# 780-00019_Rev3_Pg1.net
KiCad netlist of a schematic drawn in Altium Designer
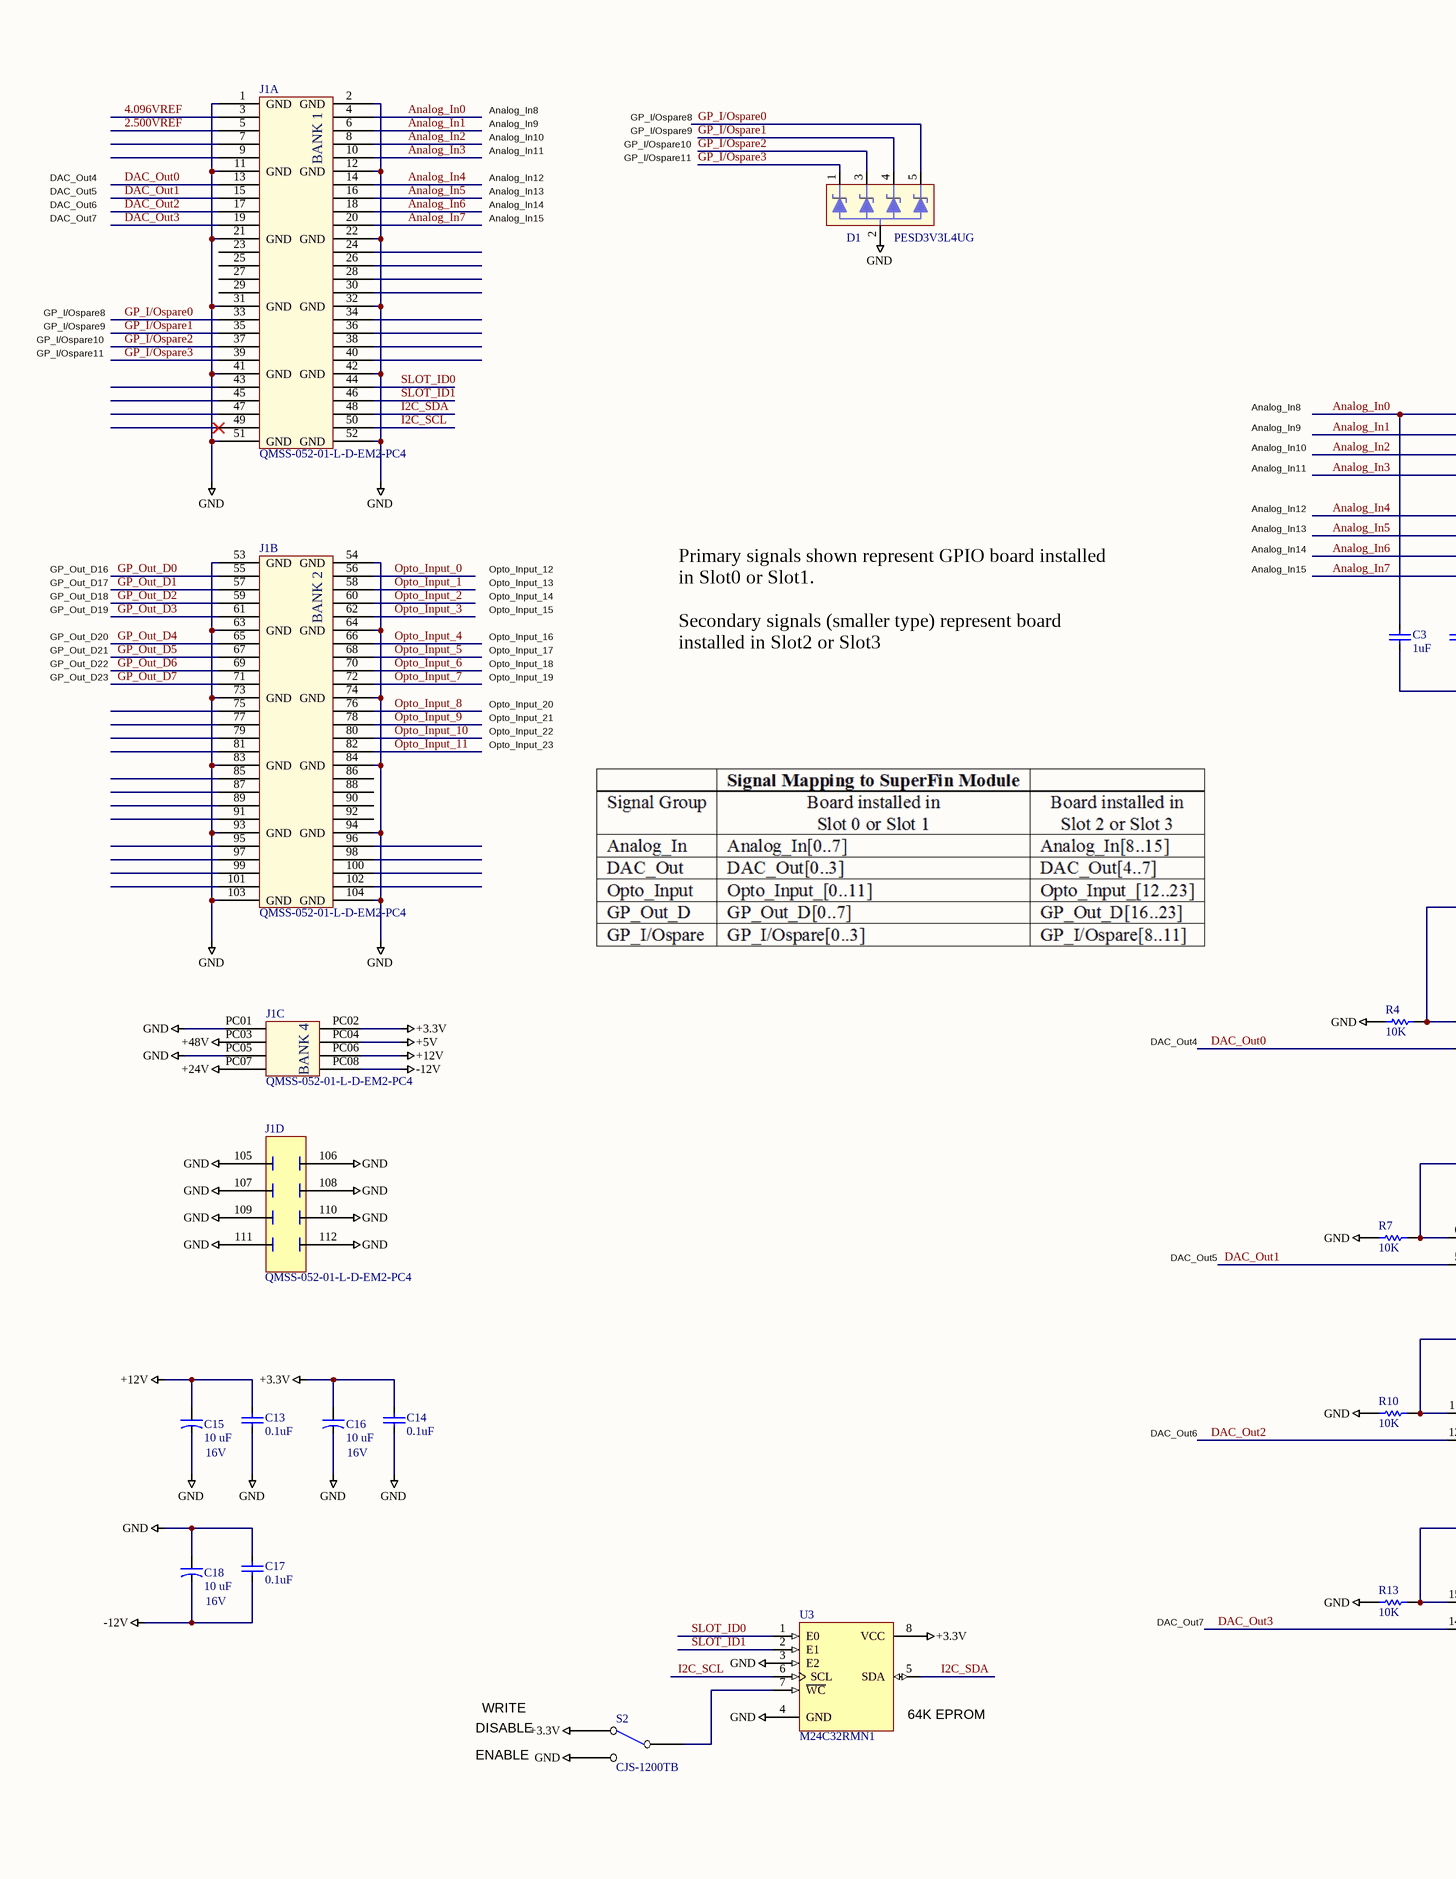
[diagram p0: 780-00019 Rev3 Pg1.SchDoc, left]
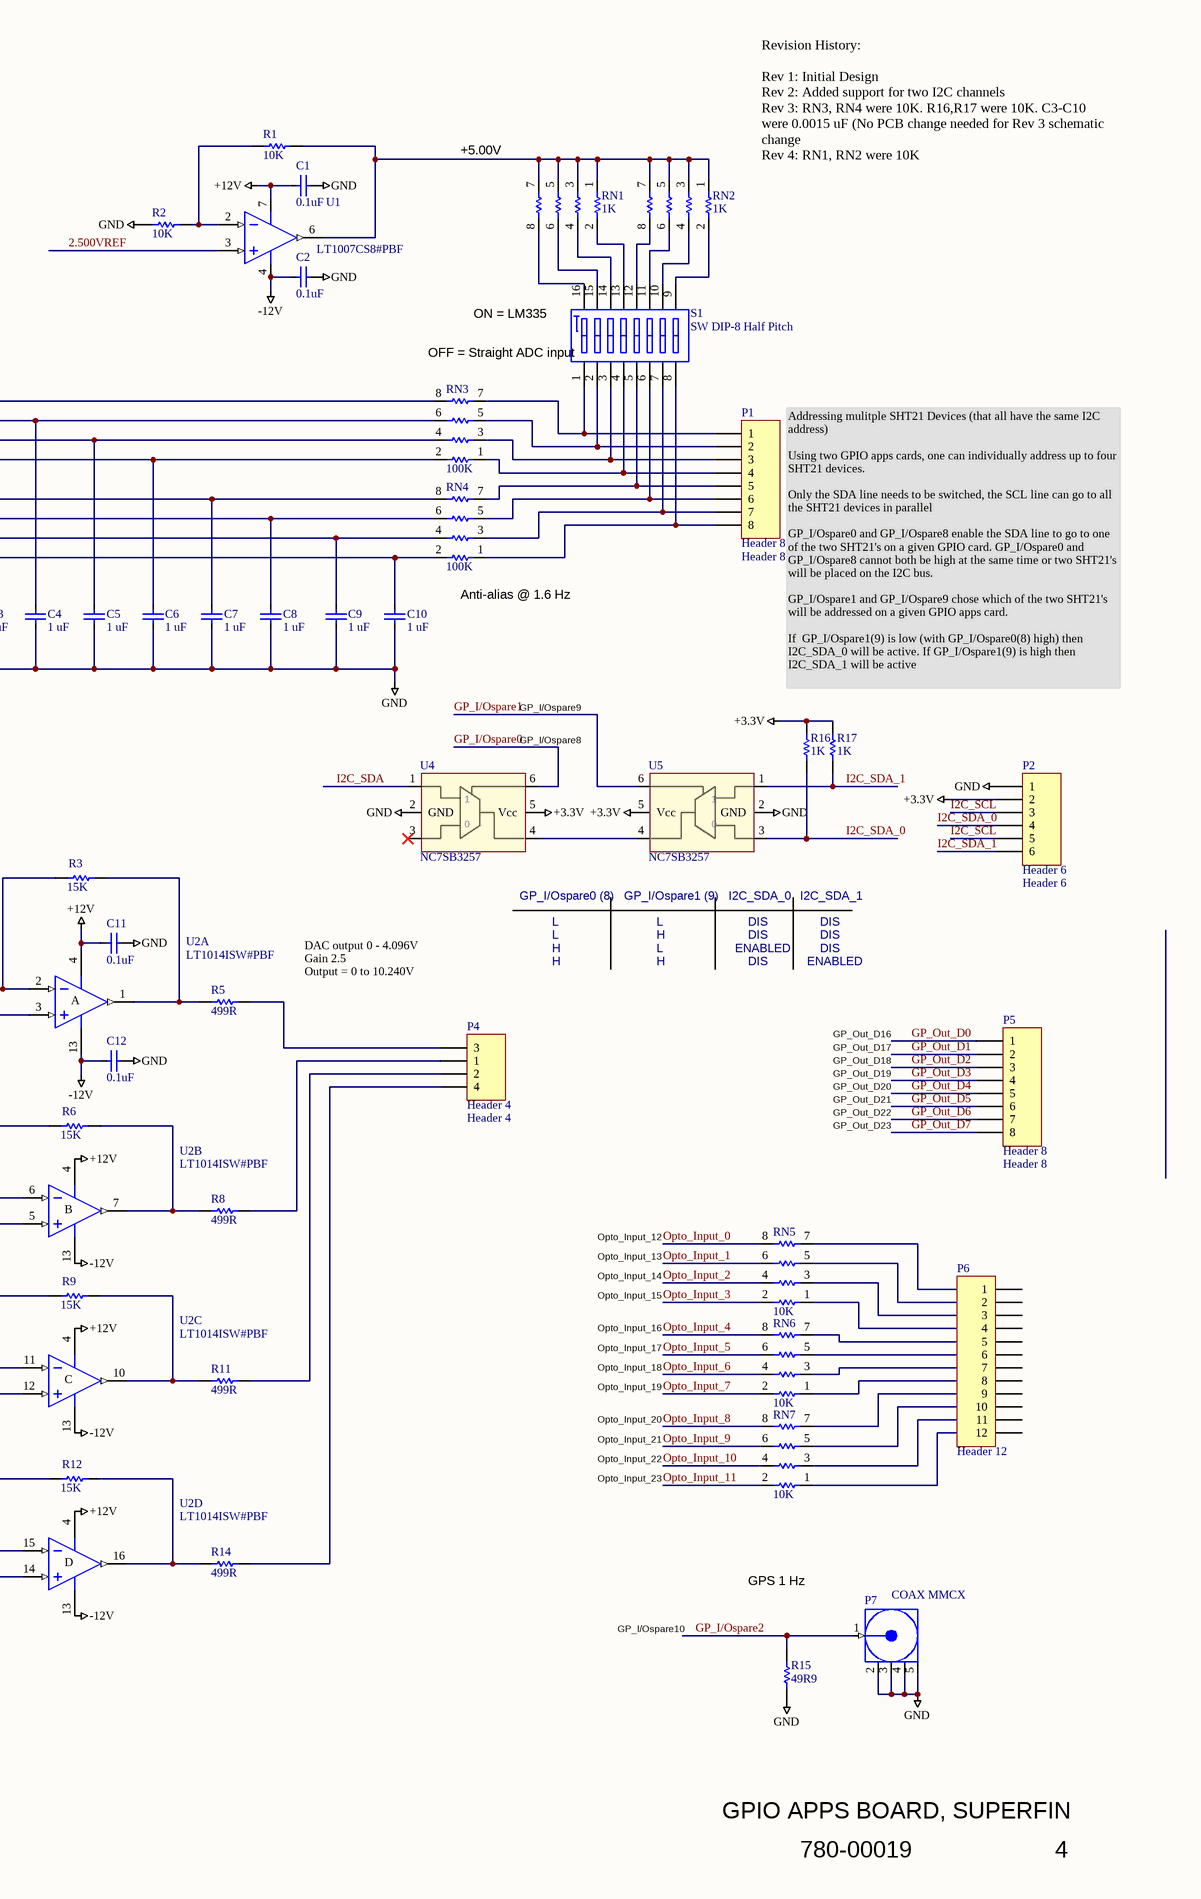
[diagram p1: 780-00019 Rev3 Pg1.SchDoc, right]

(export (version "E")
  (design (tool "Eeschema 10.0.6"))
  (components
    (comp (ref "C1")
      (value "0.1uF")
      (footprint "SMD_0805")
      (description "Capacitor")
      (fields (field (name "Comment") "Cap SMD"))
      (libsource (lib "Richs Schematic Components") (part "Cap SMD"))
    )
    (comp (ref "C2")
      (value "0.1uF")
      (footprint "SMD_0805")
      (description "Capacitor")
      (fields (field (name "Comment") "Cap SMD"))
      (libsource (lib "Richs Schematic Components") (part "Cap SMD"))
    )
    (comp (ref "C3")
      (value "1uF")
      (footprint "SMD_0805")
      (description "Capacitor NP0")
      (fields (field (name "MANUFACTURER") "Murata") (field (name "Comment") "Cap SMD"))
      (libsource (lib "Richs Schematic Components") (part "Cap SMD"))
    )
    (comp (ref "C4")
      (value "1 uF")
      (footprint "SMD_0805")
      (description "Capacitor NP0")
      (fields (field (name "MANUFACTURER") "Murata") (field (name "Comment") "Cap SMD"))
      (libsource (lib "Richs Schematic Components") (part "Cap SMD"))
    )
    (comp (ref "C5")
      (value "1 uF")
      (footprint "SMD_0805")
      (description "Capacitor NP0")
      (fields (field (name "MANUFACTURER") "Murata") (field (name "Comment") "Cap SMD"))
      (libsource (lib "Richs Schematic Components") (part "Cap SMD"))
    )
    (comp (ref "C6")
      (value "1 uF")
      (footprint "SMD_0805")
      (description "Capacitor NP0")
      (fields (field (name "MANUFACTURER") "Murata") (field (name "Comment") "Cap SMD"))
      (libsource (lib "Richs Schematic Components") (part "Cap SMD"))
    )
    (comp (ref "C7")
      (value "1 uF")
      (footprint "SMD_0805")
      (description "Capacitor NP0")
      (fields (field (name "MANUFACTURER") "Murata") (field (name "Comment") "Cap SMD"))
      (libsource (lib "Richs Schematic Components") (part "Cap SMD"))
    )
    (comp (ref "C8")
      (value "1 uF")
      (footprint "SMD_0805")
      (description "Capacitor NP0")
      (fields (field (name "MANUFACTURER") "Murata") (field (name "Comment") "Cap SMD"))
      (libsource (lib "Richs Schematic Components") (part "Cap SMD"))
    )
    (comp (ref "C9")
      (value "1 uF")
      (footprint "SMD_0805")
      (description "Capacitor NP0")
      (fields (field (name "MANUFACTURER") "Murata") (field (name "Comment") "Cap SMD"))
      (libsource (lib "Richs Schematic Components") (part "Cap SMD"))
    )
    (comp (ref "C10")
      (value "1 uF")
      (footprint "SMD_0805")
      (description "Capacitor NP0")
      (fields (field (name "MANUFACTURER") "Murata") (field (name "Comment") "Cap SMD"))
      (libsource (lib "Richs Schematic Components") (part "Cap SMD"))
    )
    (comp (ref "C11")
      (value "0.1uF")
      (footprint "SMD_0805")
      (description "Capacitor")
      (fields (field (name "Comment") "Cap SMD"))
      (libsource (lib "Richs Schematic Components") (part "Cap SMD"))
    )
    (comp (ref "C12")
      (value "0.1uF")
      (footprint "SMD_0805")
      (description "Capacitor")
      (fields (field (name "Comment") "Cap SMD"))
      (libsource (lib "Richs Schematic Components") (part "Cap SMD"))
    )
    (comp (ref "C13")
      (value "0.1uF")
      (footprint "SMD_0805")
      (description "Capacitor")
      (fields (field (name "Comment") "Cap SMD"))
      (libsource (lib "Richs Schematic Components") (part "Cap SMD"))
    )
    (comp (ref "C14")
      (value "0.1uF")
      (footprint "SMD_0805")
      (description "Capacitor")
      (fields (field (name "Comment") "Cap SMD"))
      (libsource (lib "Richs Schematic Components") (part "Cap SMD"))
    )
    (comp (ref "C15")
      (value "16V")
      (footprint "SMD_CAP_3216")
      (description "outline 3.2mm x 1.6mm")
      (fields (field (name "MANUFACTURER") "KEMET") (field (name "ALTIUM_VALUE") "10 uF"))
      (libsource (lib "Richs Schematic Components") (part "Cap Tant 16V"))
    )
    (comp (ref "C16")
      (value "16V")
      (footprint "SMD_CAP_3216")
      (description "outline 3.2mm x 1.6mm")
      (fields (field (name "MANUFACTURER") "KEMET") (field (name "ALTIUM_VALUE") "10 uF"))
      (libsource (lib "Richs Schematic Components") (part "Cap Tant 16V"))
    )
    (comp (ref "C17")
      (value "0.1uF")
      (footprint "SMD_0805")
      (description "Capacitor")
      (fields (field (name "Comment") "Cap SMD"))
      (libsource (lib "Richs Schematic Components") (part "Cap SMD"))
    )
    (comp (ref "C18")
      (value "16V")
      (footprint "SMD_CAP_3216")
      (description "outline 3.2mm x 1.6mm")
      (fields (field (name "MANUFACTURER") "KEMET") (field (name "ALTIUM_VALUE") "10 uF"))
      (libsource (lib "Richs Schematic Components") (part "Cap Tant 16V"))
    )
    (comp (ref "D1")
      (value "PESD3V3L4UG")
      (footprint "SOT-353")
      (description "Quad ESD Diode 3.3V")
      (fields (field (name "MANUFACTURER") "NXP"))
      (libsource (lib "Richs Schematic Components") (part "ESD Diode 3.3V Quad"))
    )
    (comp (ref "J1")
      (value "QMSS-052-01-L-D-EM2-PC4")
      (footprint "QMS EDGE PWR PINS - 104 pin")
      (description "SAMTEC QMSS EDGE W/PWR PINS")
      (fields (field (name "MANUFACTURER") "SAMTEC") (field (name "Comment") "QMSS-EM-PC4-104pin"))
      (libsource (lib "Richs Schematic Components") (part "QMSS-EM-PC4-104pin"))
    )
    (comp (ref "P1")
      (value "Header 8")
      (footprint "HDR1X8 for IDC")
      (description "Header, 8-Pin")
      (fields (field (name "MANUFACTURER") "tyco") (field (name "ALTIUM_VALUE") "Header 8"))
      (libsource (lib "Richs Schematic Components") (part "Header 8"))
    )
    (comp (ref "P2")
      (value "Header 6")
      (footprint "HDR1X6 for IDC")
      (description "Header, 6-Pin")
      (fields (field (name "ALTIUM_VALUE") "Header 6"))
      (libsource (lib "Richs Schematic Components") (part "Header 6"))
    )
    (comp (ref "P4")
      (value "Header 4")
      (footprint "HDR1X4 for IDC")
      (description "Header, 4-Pin")
      (fields (field (name "ALTIUM_VALUE") "Header 4"))
      (libsource (lib "Richs Schematic Components") (part "Header 4"))
    )
    (comp (ref "P5")
      (value "Header 8")
      (footprint "HDR1X8 for IDC")
      (description "Header, 8-Pin")
      (fields (field (name "MANUFACTURER") "tyco") (field (name "ALTIUM_VALUE") "Header 8"))
      (libsource (lib "Richs Schematic Components") (part "Header 8"))
    )
    (comp (ref "P6")
      (value "Header 12")
      (footprint "HDR1X12 for IDC")
      (description "Header, 12-Pin")
      (fields (field (name "MANUFACTURER") "Tyco"))
      (libsource (lib "Richs Schematic Components") (part "Header 12"))
    )
    (comp (ref "P7")
      (value "COAX MMCX")
      (footprint "Miscellaneous Connectors:MMCX2.54-V5")
      (description "RF Coaxial PCB Connector, MMCX; Thru-Hole, Vertical Mount Plug,  50 Ohm Impedance")
      (fields (field (name "MANUFACTURER") "Emerson"))
      (libsource (lib "Richs Schematic Components") (part "COAX-M"))
    )
    (comp (ref "R1")
      (value "10K")
      (footprint "SMD_0805")
      (description "Resistor 0805")
      (fields (field (name "MANUFACTURER") "Vishay/Dale") (field (name "Comment") "Res 0805"))
      (libsource (lib "Richs Schematic Components") (part "Res SMD"))
    )
    (comp (ref "R2")
      (value "10K")
      (footprint "SMD_0805")
      (description "Resistor 0805")
      (fields (field (name "MANUFACTURER") "Vishay/Dale") (field (name "Comment") "Res 0805"))
      (libsource (lib "Richs Schematic Components") (part "Res SMD"))
    )
    (comp (ref "R3")
      (value "15K")
      (footprint "SMD_0805")
      (description "Resistor 0805")
      (fields (field (name "MANUFACTURER") "Vishay/Dale") (field (name "Comment") "Res 0805"))
      (libsource (lib "Richs Schematic Components") (part "Res SMD"))
    )
    (comp (ref "R4")
      (value "10K")
      (footprint "SMD_0805")
      (description "Resistor 0805")
      (fields (field (name "MANUFACTURER") "Vishay/Dale") (field (name "Comment") "Res 0805"))
      (libsource (lib "Richs Schematic Components") (part "Res SMD"))
    )
    (comp (ref "R5")
      (value "499R")
      (footprint "SMD_0805")
      (description "Resistor 0805")
      (fields (field (name "MANUFACTURER") "Vishay/Dale") (field (name "Comment") "Res 0805"))
      (libsource (lib "Richs Schematic Components") (part "Res SMD"))
    )
    (comp (ref "R6")
      (value "15K")
      (footprint "SMD_0805")
      (description "Resistor 0805")
      (fields (field (name "MANUFACTURER") "Vishay/Dale") (field (name "Comment") "Res 0805"))
      (libsource (lib "Richs Schematic Components") (part "Res SMD"))
    )
    (comp (ref "R7")
      (value "10K")
      (footprint "SMD_0805")
      (description "Resistor 0805")
      (fields (field (name "MANUFACTURER") "Vishay/Dale") (field (name "Comment") "Res 0805"))
      (libsource (lib "Richs Schematic Components") (part "Res SMD"))
    )
    (comp (ref "R8")
      (value "499R")
      (footprint "SMD_0805")
      (description "Resistor 0805")
      (fields (field (name "MANUFACTURER") "Vishay/Dale") (field (name "Comment") "Res 0805"))
      (libsource (lib "Richs Schematic Components") (part "Res SMD"))
    )
    (comp (ref "R9")
      (value "15K")
      (footprint "SMD_0805")
      (description "Resistor 0805")
      (fields (field (name "MANUFACTURER") "Vishay/Dale") (field (name "Comment") "Res 0805"))
      (libsource (lib "Richs Schematic Components") (part "Res SMD"))
    )
    (comp (ref "R10")
      (value "10K")
      (footprint "SMD_0805")
      (description "Resistor 0805")
      (fields (field (name "MANUFACTURER") "Vishay/Dale") (field (name "Comment") "Res 0805"))
      (libsource (lib "Richs Schematic Components") (part "Res SMD"))
    )
    (comp (ref "R11")
      (value "499R")
      (footprint "SMD_0805")
      (description "Resistor 0805")
      (fields (field (name "MANUFACTURER") "Vishay/Dale") (field (name "Comment") "Res 0805"))
      (libsource (lib "Richs Schematic Components") (part "Res SMD"))
    )
    (comp (ref "R12")
      (value "15K")
      (footprint "SMD_0805")
      (description "Resistor 0805")
      (fields (field (name "MANUFACTURER") "Vishay/Dale") (field (name "Comment") "Res 0805"))
      (libsource (lib "Richs Schematic Components") (part "Res SMD"))
    )
    (comp (ref "R13")
      (value "10K")
      (footprint "SMD_0805")
      (description "Resistor 0805")
      (fields (field (name "MANUFACTURER") "Vishay/Dale") (field (name "Comment") "Res 0805"))
      (libsource (lib "Richs Schematic Components") (part "Res SMD"))
    )
    (comp (ref "R14")
      (value "499R")
      (footprint "SMD_0805")
      (description "Resistor 0805")
      (fields (field (name "MANUFACTURER") "Vishay/Dale") (field (name "Comment") "Res 0805"))
      (libsource (lib "Richs Schematic Components") (part "Res SMD"))
    )
    (comp (ref "R15")
      (value "49R9")
      (footprint "SMD_0805")
      (description "Resistor 0805")
      (fields (field (name "MANUFACTURER") "Vishay/Dale") (field (name "Comment") "Res 0805"))
      (libsource (lib "Richs Schematic Components") (part "Res SMD"))
    )
    (comp (ref "R16")
      (value "1K")
      (footprint "SMD_0805")
      (description "Resistor 0805")
      (fields (field (name "MANUFACTURER") "Vishay/Dale") (field (name "Comment") "Res 0805"))
      (libsource (lib "Richs Schematic Components") (part "Res SMD"))
    )
    (comp (ref "R17")
      (value "1K")
      (footprint "SMD_0805")
      (description "Resistor 0805")
      (fields (field (name "MANUFACTURER") "Vishay/Dale") (field (name "Comment") "Res 0805"))
      (libsource (lib "Richs Schematic Components") (part "Res SMD"))
    )
    (comp (ref "RN1")
      (value "1K")
      (footprint "RES ARRAY 0603 x 4")
      (description "Resistor Array 4 Isolated")
      (fields (field (name "Comment") "RES ARRAY  x4 1K"))
      (libsource (lib "Richs Schematic Components") (part "RES ARRAY  x4 10K"))
    )
    (comp (ref "RN2")
      (value "1K")
      (footprint "RES ARRAY 0603 x 4")
      (description "Resistor Array 4 Isolated")
      (fields (field (name "Comment") "RES ARRAY  x4 1K"))
      (libsource (lib "Richs Schematic Components") (part "RES ARRAY  x4 10K"))
    )
    (comp (ref "RN3")
      (value "100K")
      (footprint "RES ARRAY 0603 x 4")
      (description "Resistor Array 4 Isolated")
      (fields (field (name "MANUFACTURER") "PANASONIC - ECG") (field (name "Comment") "RES ARRAY  x4 10K"))
      (libsource (lib "Richs Schematic Components") (part "RES ARRAY  x4 10K"))
    )
    (comp (ref "RN4")
      (value "100K")
      (footprint "RES ARRAY 0603 x 4")
      (description "Resistor Array 4 Isolated")
      (fields (field (name "MANUFACTURER") "PANASONIC - ECG") (field (name "Comment") "RES ARRAY  x4 10K"))
      (libsource (lib "Richs Schematic Components") (part "RES ARRAY  x4 10K"))
    )
    (comp (ref "RN5")
      (value "10K")
      (footprint "RES ARRAY 0603 x 4")
      (description "Resistor Array 4 Isolated")
      (fields (field (name "MANUFACTURER") "PANASONIC - ECG") (field (name "Comment") "RES ARRAY  x4 10K"))
      (libsource (lib "Richs Schematic Components") (part "RES ARRAY  x4 10K"))
    )
    (comp (ref "RN6")
      (value "10K")
      (footprint "RES ARRAY 0603 x 4")
      (description "Resistor Array 4 Isolated")
      (fields (field (name "MANUFACTURER") "PANASONIC - ECG") (field (name "Comment") "RES ARRAY  x4 10K"))
      (libsource (lib "Richs Schematic Components") (part "RES ARRAY  x4 10K"))
    )
    (comp (ref "RN7")
      (value "10K")
      (footprint "RES ARRAY 0603 x 4")
      (description "Resistor Array 4 Isolated")
      (fields (field (name "MANUFACTURER") "PANASONIC - ECG") (field (name "Comment") "RES ARRAY  x4 10K"))
      (libsource (lib "Richs Schematic Components") (part "RES ARRAY  x4 10K"))
    )
    (comp (ref "S1")
      (value "SW DIP-8 Half Pitch")
      (footprint "SW DIP 8 pos half pitch")
      (description "DIP Switch, 8 Position, SPST")
      (fields (field (name "MANUFACTURER") "GrayHill"))
      (libsource (lib "Richs Schematic Components") (part "SW DIP-8 Half Pitch"))
    )
    (comp (ref "S2")
      (value "CJS-1200TB")
      (footprint "CAS-120B")
      (fields (field (name "MANUFACTURER") "Copal Electronics"))
      (libsource (lib "JON_1_Library") (part "SW_SPDT_DOUG"))
    )
    (comp (ref "U1")
      (value "LT1007CS8#PBF")
      (footprint "S8_M")
      (description "Low Noise BJT input opamp")
      (fields (field (name "MANUFACTURER") "Linear Tech"))
      (libsource (lib "Richs Schematic Components") (part "LT1007CS8#PBF"))
    )
    (comp (ref "U2")
      (value "LT1014ISW#PBF")
      (footprint "SW16_N")
      (description "Quad Precision Operational Amplifier")
      (fields (field (name "MANUFACTURER") "Linear Tech"))
      (libsource (lib "LT Operational Amplifier") (part "LT1014ISW#PBF"))
    )
    (comp (ref "U3")
      (value "M24C32RMN1")
      (footprint "SOP8_N")
      (description "32 Kbit Serial I²C Bus EEPROM")
      (fields (field (name "MANUFACTURER") "ST Micro"))
      (libsource (lib "ST Memory EEPROM Serial") (part "M24C32RMN1"))
    )
    (comp (ref "U4")
      (value "NC7SB3257")
      (footprint "SC70-LT6_M")
      (description "Mux/Demux Bus Switch")
      (fields (field (name "MANUFACTURER") "Fairchild"))
      (libsource (lib "") (part "MUX 2{colon}1_1"))
    )
    (comp (ref "U5")
      (value "NC7SB3257")
      (footprint "SC70-LT6_M")
      (description "Mux/Demux Bus Switch")
      (fields (field (name "MANUFACTURER") "Fairchild"))
      (libsource (lib "Richs Schematic Components") (part "MUX 2{colon}1"))
    )
  )
  (nets
    (net (code "1") (name "+3.3V") (class "Default")
      (node (ref "C14") (pin "1") (pinfunction "1_1") (pintype "passive"))
      (node (ref "C16") (pin "1") (pinfunction "1_1") (pintype "passive"))
      (node (ref "J1") (pin "PC02") (pinfunction "PC02_PC02") (pintype "passive"))
      (node (ref "P2") (pin "2") (pinfunction "2_2") (pintype "passive"))
      (node (ref "R16") (pin "2") (pinfunction "2_2") (pintype "passive"))
      (node (ref "R17") (pin "2") (pinfunction "2_2") (pintype "passive"))
      (node (ref "S2") (pin "3") (pinfunction "NC_3") (pintype "passive"))
      (node (ref "U3") (pin "8") (pinfunction "VCC_8") (pintype "power_in"))
      (node (ref "U4") (pin "5") (pinfunction "Vcc_5") (pintype "passive"))
      (node (ref "U5") (pin "5") (pinfunction "Vcc_5") (pintype "passive"))
    )
    (net (code "2") (name "+5V") (class "Default")
      (node (ref "J1") (pin "PC04") (pinfunction "PC04_PC04") (pintype "passive"))
    )
    (net (code "3") (name "+12V") (class "Default")
      (node (ref "C1") (pin "1") (pinfunction "1_1") (pintype "passive"))
      (node (ref "C11") (pin "1") (pinfunction "1_1") (pintype "passive"))
      (node (ref "C13") (pin "1") (pinfunction "1_1") (pintype "passive"))
      (node (ref "C15") (pin "1") (pinfunction "1_1") (pintype "passive"))
      (node (ref "J1") (pin "PC06") (pinfunction "PC06_PC06") (pintype "passive"))
      (node (ref "U1") (pin "7") (pinfunction "V+_7") (pintype "power_in"))
      (node (ref "U2") (pin "4") (pinfunction "V+_4") (pintype "power_in"))
    )
    (net (code "4") (name "+24V") (class "Default")
      (node (ref "J1") (pin "PC07") (pinfunction "PC07_PC07") (pintype "passive"))
    )
    (net (code "5") (name "+48V") (class "Default")
      (node (ref "J1") (pin "PC03") (pinfunction "PC03_PC03") (pintype "passive"))
    )
    (net (code "6") (name "-12V") (class "Default")
      (node (ref "C12") (pin "1") (pinfunction "1_1") (pintype "passive"))
      (node (ref "C17") (pin "2") (pinfunction "2_2") (pintype "passive"))
      (node (ref "C18") (pin "2") (pinfunction "2_2") (pintype "passive"))
      (node (ref "C2") (pin "1") (pinfunction "1_1") (pintype "passive"))
      (node (ref "J1") (pin "PC08") (pinfunction "PC08_PC08") (pintype "passive"))
      (node (ref "U1") (pin "4") (pinfunction "V-_4") (pintype "power_in"))
      (node (ref "U2") (pin "13") (pinfunction "V-_13") (pintype "power_in"))
    )
    (net (code "7") (name "/2.500VREF") (class "Default")
      (node (ref "J1") (pin "5") (pinfunction "5_5") (pintype "passive"))
      (node (ref "U1") (pin "3") (pinfunction "IN+_3") (pintype "input"))
    )
    (net (code "8") (name "/4.096VREF") (class "Default")
      (node (ref "J1") (pin "3") (pinfunction "3_3") (pintype "passive"))
    )
    (net (code "9") (name "/Analog_In0") (class "Default")
      (node (ref "C3") (pin "2") (pinfunction "2_2") (pintype "passive"))
      (node (ref "J1") (pin "4") (pinfunction "4_4") (pintype "passive"))
      (node (ref "RN3") (pin "8") (pinfunction "8_8") (pintype "passive"))
    )
    (net (code "10") (name "/Analog_In1") (class "Default")
      (node (ref "C4") (pin "2") (pinfunction "2_2") (pintype "passive"))
      (node (ref "J1") (pin "6") (pinfunction "6_6") (pintype "passive"))
      (node (ref "RN3") (pin "6") (pinfunction "6_6") (pintype "passive"))
    )
    (net (code "11") (name "/Analog_In2") (class "Default")
      (node (ref "C5") (pin "2") (pinfunction "2_2") (pintype "passive"))
      (node (ref "J1") (pin "8") (pinfunction "8_8") (pintype "passive"))
      (node (ref "RN3") (pin "4") (pinfunction "4_4") (pintype "passive"))
    )
    (net (code "12") (name "/Analog_In3") (class "Default")
      (node (ref "C6") (pin "2") (pinfunction "2_2") (pintype "passive"))
      (node (ref "J1") (pin "10") (pinfunction "10_10") (pintype "passive"))
      (node (ref "RN3") (pin "2") (pinfunction "2_2") (pintype "passive"))
    )
    (net (code "13") (name "/Analog_In4") (class "Default")
      (node (ref "C7") (pin "2") (pinfunction "2_2") (pintype "passive"))
      (node (ref "J1") (pin "14") (pinfunction "14_14") (pintype "passive"))
      (node (ref "RN4") (pin "8") (pinfunction "8_8") (pintype "passive"))
    )
    (net (code "14") (name "/Analog_In5") (class "Default")
      (node (ref "C8") (pin "2") (pinfunction "2_2") (pintype "passive"))
      (node (ref "J1") (pin "16") (pinfunction "16_16") (pintype "passive"))
      (node (ref "RN4") (pin "6") (pinfunction "6_6") (pintype "passive"))
    )
    (net (code "15") (name "/Analog_In6") (class "Default")
      (node (ref "C9") (pin "2") (pinfunction "2_2") (pintype "passive"))
      (node (ref "J1") (pin "18") (pinfunction "18_18") (pintype "passive"))
      (node (ref "RN4") (pin "4") (pinfunction "4_4") (pintype "passive"))
    )
    (net (code "16") (name "/Analog_In7") (class "Default")
      (node (ref "C10") (pin "2") (pinfunction "2_2") (pintype "passive"))
      (node (ref "J1") (pin "20") (pinfunction "20_20") (pintype "passive"))
      (node (ref "RN4") (pin "2") (pinfunction "2_2") (pintype "passive"))
    )
    (net (code "17") (name "/DAC_Out0") (class "Default")
      (node (ref "J1") (pin "13") (pinfunction "13_13") (pintype "passive"))
      (node (ref "U2") (pin "3") (pinfunction "IN+_3") (pintype "input"))
    )
    (net (code "18") (name "/DAC_Out1") (class "Default")
      (node (ref "J1") (pin "15") (pinfunction "15_15") (pintype "passive"))
      (node (ref "U2") (pin "5") (pinfunction "IN+_5") (pintype "input"))
    )
    (net (code "19") (name "/DAC_Out2") (class "Default")
      (node (ref "J1") (pin "17") (pinfunction "17_17") (pintype "passive"))
      (node (ref "U2") (pin "12") (pinfunction "IN+_12") (pintype "input"))
    )
    (net (code "20") (name "/DAC_Out3") (class "Default")
      (node (ref "J1") (pin "19") (pinfunction "19_19") (pintype "passive"))
      (node (ref "U2") (pin "14") (pinfunction "IN+_14") (pintype "input"))
    )
    (net (code "21") (name "/GP_I{slash}Ospare0") (class "Default")
      (node (ref "D1") (pin "5") (pintype "passive"))
      (node (ref "J1") (pin "33") (pinfunction "33_33") (pintype "passive"))
      (node (ref "U4") (pin "6") (pinfunction "S_6") (pintype "passive"))
    )
    (net (code "22") (name "/GP_I{slash}Ospare1") (class "Default")
      (node (ref "D1") (pin "4") (pintype "passive"))
      (node (ref "J1") (pin "35") (pinfunction "35_35") (pintype "passive"))
      (node (ref "U5") (pin "6") (pinfunction "S_6") (pintype "passive"))
    )
    (net (code "23") (name "/GP_I{slash}Ospare2") (class "Default")
      (node (ref "D1") (pin "3") (pintype "passive"))
      (node (ref "J1") (pin "37") (pinfunction "37_37") (pintype "passive"))
      (node (ref "P7") (pin "1") (pinfunction "Signal_1") (pintype "input"))
      (node (ref "R15") (pin "2") (pinfunction "2_2") (pintype "passive"))
    )
    (net (code "24") (name "/GP_I{slash}Ospare3") (class "Default")
      (node (ref "D1") (pin "1") (pintype "passive"))
      (node (ref "J1") (pin "39") (pinfunction "39_39") (pintype "passive"))
    )
    (net (code "25") (name "/GP_Out_D0") (class "Default")
      (node (ref "J1") (pin "55") (pinfunction "55_55") (pintype "passive"))
      (node (ref "P5") (pin "1") (pinfunction "1_1") (pintype "passive"))
    )
    (net (code "26") (name "/GP_Out_D1") (class "Default")
      (node (ref "J1") (pin "57") (pinfunction "57_57") (pintype "passive"))
      (node (ref "P5") (pin "2") (pinfunction "2_2") (pintype "passive"))
    )
    (net (code "27") (name "/GP_Out_D2") (class "Default")
      (node (ref "J1") (pin "59") (pinfunction "59_59") (pintype "passive"))
      (node (ref "P5") (pin "3") (pinfunction "3_3") (pintype "passive"))
    )
    (net (code "28") (name "/GP_Out_D3") (class "Default")
      (node (ref "J1") (pin "61") (pinfunction "61_61") (pintype "passive"))
      (node (ref "P5") (pin "4") (pinfunction "4_4") (pintype "passive"))
    )
    (net (code "29") (name "/GP_Out_D4") (class "Default")
      (node (ref "J1") (pin "65") (pinfunction "65_65") (pintype "passive"))
      (node (ref "P5") (pin "5") (pinfunction "5_5") (pintype "passive"))
    )
    (net (code "30") (name "/GP_Out_D5") (class "Default")
      (node (ref "J1") (pin "67") (pinfunction "67_67") (pintype "passive"))
      (node (ref "P5") (pin "6") (pinfunction "6_6") (pintype "passive"))
    )
    (net (code "31") (name "/GP_Out_D6") (class "Default")
      (node (ref "J1") (pin "69") (pinfunction "69_69") (pintype "passive"))
      (node (ref "P5") (pin "7") (pinfunction "7_7") (pintype "passive"))
    )
    (net (code "32") (name "/GP_Out_D7") (class "Default")
      (node (ref "J1") (pin "71") (pinfunction "71_71") (pintype "passive"))
      (node (ref "P5") (pin "8") (pinfunction "8_8") (pintype "passive"))
    )
    (net (code "33") (name "/I2C_SCL") (class "Default")
      (node (ref "J1") (pin "50") (pinfunction "50_50") (pintype "passive"))
      (node (ref "P2") (pin "3") (pinfunction "3_3") (pintype "passive"))
      (node (ref "P2") (pin "5") (pinfunction "5_5") (pintype "passive"))
      (node (ref "U3") (pin "6") (pinfunction "SCL_6") (pintype "input"))
    )
    (net (code "34") (name "/I2C_SDA") (class "Default")
      (node (ref "J1") (pin "48") (pinfunction "48_48") (pintype "passive"))
      (node (ref "U3") (pin "5") (pinfunction "SDA_5") (pintype "bidirectional"))
      (node (ref "U4") (pin "1") (pinfunction "B1_1") (pintype "passive"))
    )
    (net (code "35") (name "/I2C_SDA_0") (class "Default")
      (node (ref "P2") (pin "4") (pinfunction "4_4") (pintype "passive"))
      (node (ref "R16") (pin "1") (pinfunction "1_1") (pintype "passive"))
      (node (ref "U5") (pin "3") (pinfunction "B0_3") (pintype "passive"))
    )
    (net (code "36") (name "/I2C_SDA_1") (class "Default")
      (node (ref "P2") (pin "6") (pinfunction "6_6") (pintype "passive"))
      (node (ref "R17") (pin "1") (pinfunction "1_1") (pintype "passive"))
      (node (ref "U5") (pin "1") (pinfunction "B1_1") (pintype "passive"))
    )
    (net (code "37") (name "/Opto_Input_0") (class "Default")
      (node (ref "J1") (pin "56") (pinfunction "56_56") (pintype "passive"))
      (node (ref "RN5") (pin "8") (pinfunction "8_8") (pintype "passive"))
    )
    (net (code "38") (name "/Opto_Input_1") (class "Default")
      (node (ref "J1") (pin "58") (pinfunction "58_58") (pintype "passive"))
      (node (ref "RN5") (pin "6") (pinfunction "6_6") (pintype "passive"))
    )
    (net (code "39") (name "/Opto_Input_2") (class "Default")
      (node (ref "J1") (pin "60") (pinfunction "60_60") (pintype "passive"))
      (node (ref "RN5") (pin "4") (pinfunction "4_4") (pintype "passive"))
    )
    (net (code "40") (name "/Opto_Input_3") (class "Default")
      (node (ref "J1") (pin "62") (pinfunction "62_62") (pintype "passive"))
      (node (ref "RN5") (pin "2") (pinfunction "2_2") (pintype "passive"))
    )
    (net (code "41") (name "/Opto_Input_4") (class "Default")
      (node (ref "J1") (pin "66") (pinfunction "66_66") (pintype "passive"))
      (node (ref "RN6") (pin "8") (pinfunction "8_8") (pintype "passive"))
    )
    (net (code "42") (name "/Opto_Input_5") (class "Default")
      (node (ref "J1") (pin "68") (pinfunction "68_68") (pintype "passive"))
      (node (ref "RN6") (pin "6") (pinfunction "6_6") (pintype "passive"))
    )
    (net (code "43") (name "/Opto_Input_6") (class "Default")
      (node (ref "J1") (pin "70") (pinfunction "70_70") (pintype "passive"))
      (node (ref "RN6") (pin "4") (pinfunction "4_4") (pintype "passive"))
    )
    (net (code "44") (name "/Opto_Input_7") (class "Default")
      (node (ref "J1") (pin "72") (pinfunction "72_72") (pintype "passive"))
      (node (ref "RN6") (pin "2") (pinfunction "2_2") (pintype "passive"))
    )
    (net (code "45") (name "/Opto_Input_8") (class "Default")
      (node (ref "J1") (pin "76") (pinfunction "76_76") (pintype "passive"))
      (node (ref "RN7") (pin "8") (pinfunction "8_8") (pintype "passive"))
    )
    (net (code "46") (name "/Opto_Input_9") (class "Default")
      (node (ref "J1") (pin "78") (pinfunction "78_78") (pintype "passive"))
      (node (ref "RN7") (pin "6") (pinfunction "6_6") (pintype "passive"))
    )
    (net (code "47") (name "/Opto_Input_10") (class "Default")
      (node (ref "J1") (pin "80") (pinfunction "80_80") (pintype "passive"))
      (node (ref "RN7") (pin "4") (pinfunction "4_4") (pintype "passive"))
    )
    (net (code "48") (name "/Opto_Input_11") (class "Default")
      (node (ref "J1") (pin "82") (pinfunction "82_82") (pintype "passive"))
      (node (ref "RN7") (pin "2") (pinfunction "2_2") (pintype "passive"))
    )
    (net (code "49") (name "/SLOT_ID0") (class "Default")
      (node (ref "J1") (pin "44") (pinfunction "44_44") (pintype "passive"))
      (node (ref "U3") (pin "1") (pinfunction "E0_1") (pintype "input"))
    )
    (net (code "50") (name "/SLOT_ID1") (class "Default")
      (node (ref "J1") (pin "46") (pinfunction "46_46") (pintype "passive"))
      (node (ref "U3") (pin "2") (pinfunction "E1_2") (pintype "input"))
    )
    (net (code "51") (name "GND") (class "Default")
      (node (ref "C1") (pin "2") (pinfunction "2_2") (pintype "passive"))
      (node (ref "C10") (pin "1") (pinfunction "1_1") (pintype "passive"))
      (node (ref "C11") (pin "2") (pinfunction "2_2") (pintype "passive"))
      (node (ref "C12") (pin "2") (pinfunction "2_2") (pintype "passive"))
      (node (ref "C13") (pin "2") (pinfunction "2_2") (pintype "passive"))
      (node (ref "C14") (pin "2") (pinfunction "2_2") (pintype "passive"))
      (node (ref "C15") (pin "2") (pinfunction "2_2") (pintype "passive"))
      (node (ref "C16") (pin "2") (pinfunction "2_2") (pintype "passive"))
      (node (ref "C17") (pin "1") (pinfunction "1_1") (pintype "passive"))
      (node (ref "C18") (pin "1") (pinfunction "1_1") (pintype "passive"))
      (node (ref "C2") (pin "2") (pinfunction "2_2") (pintype "passive"))
      (node (ref "C3") (pin "1") (pinfunction "1_1") (pintype "passive"))
      (node (ref "C4") (pin "1") (pinfunction "1_1") (pintype "passive"))
      (node (ref "C5") (pin "1") (pinfunction "1_1") (pintype "passive"))
      (node (ref "C6") (pin "1") (pinfunction "1_1") (pintype "passive"))
      (node (ref "C7") (pin "1") (pinfunction "1_1") (pintype "passive"))
      (node (ref "C8") (pin "1") (pinfunction "1_1") (pintype "passive"))
      (node (ref "C9") (pin "1") (pinfunction "1_1") (pintype "passive"))
      (node (ref "D1") (pin "2") (pintype "passive"))
      (node (ref "J1") (pin "1") (pinfunction "GND_1") (pintype "passive"))
      (node (ref "J1") (pin "103") (pinfunction "GND_103") (pintype "passive"))
      (node (ref "J1") (pin "104") (pinfunction "GND_104") (pintype "passive"))
      (node (ref "J1") (pin "105") (pinfunction "GND_105") (pintype "passive"))
      (node (ref "J1") (pin "106") (pinfunction "GND_106") (pintype "passive"))
      (node (ref "J1") (pin "107") (pinfunction "GND_107") (pintype "passive"))
      (node (ref "J1") (pin "108") (pinfunction "GND_108") (pintype "passive"))
      (node (ref "J1") (pin "109") (pinfunction "GND_109") (pintype "passive"))
      (node (ref "J1") (pin "11") (pinfunction "GND_11") (pintype "passive"))
      (node (ref "J1") (pin "110") (pinfunction "GND_110") (pintype "passive"))
      (node (ref "J1") (pin "111") (pinfunction "GND_111") (pintype "passive"))
      (node (ref "J1") (pin "112") (pinfunction "GND_112") (pintype "passive"))
      (node (ref "J1") (pin "12") (pinfunction "GND_12") (pintype "passive"))
      (node (ref "J1") (pin "2") (pinfunction "GND_2") (pintype "passive"))
      (node (ref "J1") (pin "21") (pinfunction "GND_21") (pintype "passive"))
      (node (ref "J1") (pin "22") (pinfunction "GND_22") (pintype "passive"))
      (node (ref "J1") (pin "31") (pinfunction "GND_31") (pintype "passive"))
      (node (ref "J1") (pin "32") (pinfunction "GND_32") (pintype "passive"))
      (node (ref "J1") (pin "41") (pinfunction "GND_41") (pintype "passive"))
      (node (ref "J1") (pin "42") (pinfunction "GND_42") (pintype "passive"))
      (node (ref "J1") (pin "51") (pinfunction "GND_51") (pintype "passive"))
      (node (ref "J1") (pin "52") (pinfunction "GND_52") (pintype "passive"))
      (node (ref "J1") (pin "53") (pinfunction "GND_53") (pintype "passive"))
      (node (ref "J1") (pin "54") (pinfunction "GND_54") (pintype "passive"))
      (node (ref "J1") (pin "63") (pinfunction "GND_63") (pintype "passive"))
      (node (ref "J1") (pin "64") (pinfunction "GND_64") (pintype "passive"))
      (node (ref "J1") (pin "73") (pinfunction "GND_73") (pintype "passive"))
      (node (ref "J1") (pin "74") (pinfunction "GND_74") (pintype "passive"))
      (node (ref "J1") (pin "83") (pinfunction "GND_83") (pintype "passive"))
      (node (ref "J1") (pin "84") (pinfunction "GND_84") (pintype "passive"))
      (node (ref "J1") (pin "93") (pinfunction "GND_93") (pintype "passive"))
      (node (ref "J1") (pin "94") (pinfunction "GND_94") (pintype "passive"))
      (node (ref "J1") (pin "PC01") (pinfunction "PC01_PC01") (pintype "passive"))
      (node (ref "J1") (pin "PC05") (pinfunction "PC05_PC05") (pintype "passive"))
      (node (ref "P2") (pin "1") (pinfunction "1_1") (pintype "passive"))
      (node (ref "P7") (pin "2") (pinfunction "GND_2") (pintype "power_in"))
      (node (ref "P7") (pin "3") (pinfunction "GND_3") (pintype "power_in"))
      (node (ref "P7") (pin "4") (pinfunction "GND_4") (pintype "power_in"))
      (node (ref "P7") (pin "5") (pinfunction "GND_5") (pintype "power_in"))
      (node (ref "R10") (pin "1") (pinfunction "1_1") (pintype "passive"))
      (node (ref "R13") (pin "1") (pinfunction "1_1") (pintype "passive"))
      (node (ref "R15") (pin "1") (pinfunction "1_1") (pintype "passive"))
      (node (ref "R2") (pin "1") (pinfunction "1_1") (pintype "passive"))
      (node (ref "R4") (pin "1") (pinfunction "1_1") (pintype "passive"))
      (node (ref "R7") (pin "1") (pinfunction "1_1") (pintype "passive"))
      (node (ref "S2") (pin "1") (pinfunction "NO_1") (pintype "passive"))
      (node (ref "U3") (pin "3") (pinfunction "E2_3") (pintype "input"))
      (node (ref "U3") (pin "4") (pinfunction "GND_4") (pintype "power_in"))
      (node (ref "U4") (pin "2") (pinfunction "GND_2") (pintype "passive"))
      (node (ref "U5") (pin "2") (pinfunction "GND_2") (pintype "passive"))
    )
    (net (code "52") (name "Net-(P4-Pad1)") (class "Default")
      (node (ref "P4") (pin "1") (pinfunction "1_1") (pintype "passive"))
      (node (ref "R8") (pin "1") (pinfunction "1_1") (pintype "passive"))
    )
    (net (code "53") (name "Net-(P4-Pad2)") (class "Default")
      (node (ref "P4") (pin "2") (pinfunction "2_2") (pintype "passive"))
      (node (ref "R11") (pin "1") (pinfunction "1_1") (pintype "passive"))
    )
    (net (code "54") (name "Net-(P4-Pad3)") (class "Default")
      (node (ref "P4") (pin "3") (pinfunction "3_3") (pintype "passive"))
      (node (ref "R5") (pin "1") (pinfunction "1_1") (pintype "passive"))
    )
    (net (code "55") (name "Net-(P4-Pad4)") (class "Default")
      (node (ref "P4") (pin "4") (pinfunction "4_4") (pintype "passive"))
      (node (ref "R14") (pin "1") (pinfunction "1_1") (pintype "passive"))
    )
    (net (code "56") (name "Net-(S1-A1)") (class "Default")
      (node (ref "P1") (pin "1") (pinfunction "1_1") (pintype "passive"))
      (node (ref "RN3") (pin "7") (pinfunction "1_7") (pintype "passive"))
      (node (ref "S1") (pin "1") (pinfunction "A1_1") (pintype "passive"))
    )
    (net (code "57") (name "Net-(S1-A2)") (class "Default")
      (node (ref "P1") (pin "2") (pinfunction "2_2") (pintype "passive"))
      (node (ref "RN3") (pin "5") (pinfunction "5_5") (pintype "passive"))
      (node (ref "S1") (pin "2") (pinfunction "A2_2") (pintype "passive"))
    )
    (net (code "58") (name "Net-(S1-A3)") (class "Default")
      (node (ref "P1") (pin "3") (pinfunction "3_3") (pintype "passive"))
      (node (ref "RN3") (pin "3") (pinfunction "3_3") (pintype "passive"))
      (node (ref "S1") (pin "3") (pinfunction "A3_3") (pintype "passive"))
    )
    (net (code "59") (name "Net-(S1-A4)") (class "Default")
      (node (ref "P1") (pin "4") (pinfunction "4_4") (pintype "passive"))
      (node (ref "RN3") (pin "1") (pinfunction "1_1") (pintype "passive"))
      (node (ref "S1") (pin "4") (pinfunction "A4_4") (pintype "passive"))
    )
    (net (code "60") (name "Net-(S1-A5)") (class "Default")
      (node (ref "P1") (pin "5") (pinfunction "5_5") (pintype "passive"))
      (node (ref "RN4") (pin "7") (pinfunction "1_7") (pintype "passive"))
      (node (ref "S1") (pin "5") (pinfunction "A5_5") (pintype "passive"))
    )
    (net (code "61") (name "Net-(S1-A6)") (class "Default")
      (node (ref "P1") (pin "6") (pinfunction "6_6") (pintype "passive"))
      (node (ref "RN4") (pin "5") (pinfunction "5_5") (pintype "passive"))
      (node (ref "S1") (pin "6") (pinfunction "A6_6") (pintype "passive"))
    )
    (net (code "62") (name "Net-(S1-A7)") (class "Default")
      (node (ref "P1") (pin "7") (pinfunction "7_7") (pintype "passive"))
      (node (ref "RN4") (pin "3") (pinfunction "3_3") (pintype "passive"))
      (node (ref "S1") (pin "7") (pinfunction "A7_7") (pintype "passive"))
    )
    (net (code "63") (name "Net-(S1-A8)") (class "Default")
      (node (ref "P1") (pin "8") (pinfunction "8_8") (pintype "passive"))
      (node (ref "RN4") (pin "1") (pinfunction "1_1") (pintype "passive"))
      (node (ref "S1") (pin "8") (pinfunction "A8_8") (pintype "passive"))
    )
    (net (code "64") (name "Net-(S1-B1)") (class "Default")
      (node (ref "RN1") (pin "8") (pinfunction "8_8") (pintype "passive"))
      (node (ref "S1") (pin "16") (pinfunction "B1_16") (pintype "passive"))
    )
    (net (code "65") (name "Net-(S1-B2)") (class "Default")
      (node (ref "RN1") (pin "6") (pinfunction "6_6") (pintype "passive"))
      (node (ref "S1") (pin "15") (pinfunction "B2_15") (pintype "passive"))
    )
    (net (code "66") (name "Net-(S1-B3)") (class "Default")
      (node (ref "RN1") (pin "4") (pinfunction "4_4") (pintype "passive"))
      (node (ref "S1") (pin "14") (pinfunction "B3_14") (pintype "passive"))
    )
    (net (code "67") (name "Net-(S1-B4)") (class "Default")
      (node (ref "RN1") (pin "2") (pinfunction "2_2") (pintype "passive"))
      (node (ref "S1") (pin "13") (pinfunction "B4_13") (pintype "passive"))
    )
    (net (code "68") (name "Net-(S1-B5)") (class "Default")
      (node (ref "RN2") (pin "8") (pinfunction "8_8") (pintype "passive"))
      (node (ref "S1") (pin "12") (pinfunction "B5_12") (pintype "passive"))
    )
    (net (code "69") (name "Net-(S1-B6)") (class "Default")
      (node (ref "RN2") (pin "6") (pinfunction "6_6") (pintype "passive"))
      (node (ref "S1") (pin "11") (pinfunction "B6_11") (pintype "passive"))
    )
    (net (code "70") (name "Net-(S1-B7)") (class "Default")
      (node (ref "RN2") (pin "4") (pinfunction "4_4") (pintype "passive"))
      (node (ref "S1") (pin "10") (pinfunction "B7_10") (pintype "passive"))
    )
    (net (code "71") (name "Net-(S1-B8)") (class "Default")
      (node (ref "RN2") (pin "2") (pinfunction "2_2") (pintype "passive"))
      (node (ref "S1") (pin "9") (pinfunction "B8_9") (pintype "passive"))
    )
    (net (code "72") (name "Net-(S2-COM)") (class "Default")
      (node (ref "S2") (pin "2") (pinfunction "COM_2") (pintype "passive"))
      (node (ref "U3") (pin "7") (pinfunction "~{WC}_7") (pintype "input"))
    )
    (net (code "73") (name "Net-(U1-IN-)") (class "Default")
      (node (ref "R1") (pin "1") (pinfunction "1_1") (pintype "passive"))
      (node (ref "R2") (pin "2") (pinfunction "2_2") (pintype "passive"))
      (node (ref "U1") (pin "2") (pinfunction "IN-_2") (pintype "input"))
    )
    (net (code "74") (name "Net-(U1-OUT)") (class "Default")
      (node (ref "R1") (pin "2") (pinfunction "2_2") (pintype "passive"))
      (node (ref "RN1") (pin "1") (pinfunction "1_1") (pintype "passive"))
      (node (ref "RN1") (pin "3") (pinfunction "3_3") (pintype "passive"))
      (node (ref "RN1") (pin "5") (pinfunction "5_5") (pintype "passive"))
      (node (ref "RN1") (pin "7") (pinfunction "1_7") (pintype "passive"))
      (node (ref "RN2") (pin "1") (pinfunction "1_1") (pintype "passive"))
      (node (ref "RN2") (pin "3") (pinfunction "3_3") (pintype "passive"))
      (node (ref "RN2") (pin "5") (pinfunction "5_5") (pintype "passive"))
      (node (ref "RN2") (pin "7") (pinfunction "1_7") (pintype "passive"))
      (node (ref "U1") (pin "6") (pinfunction "OUT_6") (pintype "output"))
    )
    (net (code "75") (name "Net-(U2A-IN-)") (class "Default")
      (node (ref "R3") (pin "1") (pinfunction "1_1") (pintype "passive"))
      (node (ref "R4") (pin "2") (pinfunction "2_2") (pintype "passive"))
      (node (ref "U2") (pin "2") (pinfunction "IN-_2") (pintype "input"))
    )
    (net (code "76") (name "Net-(U2A-OUT)") (class "Default")
      (node (ref "R3") (pin "2") (pinfunction "2_2") (pintype "passive"))
      (node (ref "R5") (pin "2") (pinfunction "2_2") (pintype "passive"))
      (node (ref "U2") (pin "1") (pinfunction "OUT_1") (pintype "output"))
    )
    (net (code "77") (name "Net-(U2B-IN-)") (class "Default")
      (node (ref "R6") (pin "1") (pinfunction "1_1") (pintype "passive"))
      (node (ref "R7") (pin "2") (pinfunction "2_2") (pintype "passive"))
      (node (ref "U2") (pin "6") (pinfunction "IN-_6") (pintype "input"))
    )
    (net (code "78") (name "Net-(U2B-OUT)") (class "Default")
      (node (ref "R6") (pin "2") (pinfunction "2_2") (pintype "passive"))
      (node (ref "R8") (pin "2") (pinfunction "2_2") (pintype "passive"))
      (node (ref "U2") (pin "7") (pinfunction "OUT_7") (pintype "output"))
    )
    (net (code "79") (name "Net-(U2C-IN-)") (class "Default")
      (node (ref "R10") (pin "2") (pinfunction "2_2") (pintype "passive"))
      (node (ref "R9") (pin "1") (pinfunction "1_1") (pintype "passive"))
      (node (ref "U2") (pin "11") (pinfunction "IN-_11") (pintype "input"))
    )
    (net (code "80") (name "Net-(U2C-OUT)") (class "Default")
      (node (ref "R11") (pin "2") (pinfunction "2_2") (pintype "passive"))
      (node (ref "R9") (pin "2") (pinfunction "2_2") (pintype "passive"))
      (node (ref "U2") (pin "10") (pinfunction "OUT_10") (pintype "output"))
    )
    (net (code "81") (name "Net-(U2D-IN-)") (class "Default")
      (node (ref "R12") (pin "1") (pinfunction "1_1") (pintype "passive"))
      (node (ref "R13") (pin "2") (pinfunction "2_2") (pintype "passive"))
      (node (ref "U2") (pin "15") (pinfunction "IN-_15") (pintype "input"))
    )
    (net (code "82") (name "Net-(U2D-OUT)") (class "Default")
      (node (ref "R12") (pin "2") (pinfunction "2_2") (pintype "passive"))
      (node (ref "R14") (pin "2") (pinfunction "2_2") (pintype "passive"))
      (node (ref "U2") (pin "16") (pinfunction "OUT_16") (pintype "output"))
    )
    (net (code "83") (name "Net-(U4-A)") (class "Default")
      (node (ref "U4") (pin "4") (pinfunction "A_4") (pintype "passive"))
      (node (ref "U5") (pin "4") (pinfunction "A_4") (pintype "passive"))
    )
    (net (code "84") (name "unconnected-(J1-Pad7)") (class "Default")
      (node (ref "J1") (pin "7") (pinfunction "7_7") (pintype "passive"))
    )
    (net (code "85") (name "unconnected-(J1-Pad9)") (class "Default")
      (node (ref "J1") (pin "9") (pinfunction "9_9") (pintype "passive"))
    )
    (net (code "86") (name "unconnected-(J1-Pad23)") (class "Default")
      (node (ref "J1") (pin "23") (pinfunction "23_23") (pintype "passive"))
    )
    (net (code "87") (name "unconnected-(J1-Pad24)") (class "Default")
      (node (ref "J1") (pin "24") (pinfunction "24_24") (pintype "passive"))
    )
    (net (code "88") (name "unconnected-(J1-Pad25)") (class "Default")
      (node (ref "J1") (pin "25") (pinfunction "25_25") (pintype "passive"))
    )
    (net (code "89") (name "unconnected-(J1-Pad26)") (class "Default")
      (node (ref "J1") (pin "26") (pinfunction "26_26") (pintype "passive"))
    )
    (net (code "90") (name "unconnected-(J1-Pad27)") (class "Default")
      (node (ref "J1") (pin "27") (pinfunction "27_27") (pintype "passive"))
    )
    (net (code "91") (name "unconnected-(J1-Pad28)") (class "Default")
      (node (ref "J1") (pin "28") (pinfunction "28_28") (pintype "passive"))
    )
    (net (code "92") (name "unconnected-(J1-Pad29)") (class "Default")
      (node (ref "J1") (pin "29") (pinfunction "29_29") (pintype "passive"))
    )
    (net (code "93") (name "unconnected-(J1-Pad30)") (class "Default")
      (node (ref "J1") (pin "30") (pinfunction "30_30") (pintype "passive"))
    )
    (net (code "94") (name "unconnected-(J1-Pad34)") (class "Default")
      (node (ref "J1") (pin "34") (pinfunction "34_34") (pintype "passive"))
    )
    (net (code "95") (name "unconnected-(J1-Pad36)") (class "Default")
      (node (ref "J1") (pin "36") (pinfunction "36_36") (pintype "passive"))
    )
    (net (code "96") (name "unconnected-(J1-Pad38)") (class "Default")
      (node (ref "J1") (pin "38") (pinfunction "38_38") (pintype "passive"))
    )
    (net (code "97") (name "unconnected-(J1-Pad40)") (class "Default")
      (node (ref "J1") (pin "40") (pinfunction "40_40") (pintype "passive"))
    )
    (net (code "98") (name "unconnected-(J1-Pad43)") (class "Default")
      (node (ref "J1") (pin "43") (pinfunction "43_43") (pintype "passive"))
    )
    (net (code "99") (name "unconnected-(J1-Pad45)") (class "Default")
      (node (ref "J1") (pin "45") (pinfunction "45_45") (pintype "passive"))
    )
    (net (code "100") (name "unconnected-(J1-Pad47)") (class "Default")
      (node (ref "J1") (pin "47") (pinfunction "47_47") (pintype "passive"))
    )
    (net (code "101") (name "unconnected-(J1-Pad49)") (class "Default")
      (node (ref "J1") (pin "49") (pinfunction "49_49") (pintype "passive+no_connect"))
    )
    (net (code "102") (name "unconnected-(J1-Pad75)") (class "Default")
      (node (ref "J1") (pin "75") (pinfunction "75_75") (pintype "passive"))
    )
    (net (code "103") (name "unconnected-(J1-Pad77)") (class "Default")
      (node (ref "J1") (pin "77") (pinfunction "77_77") (pintype "passive"))
    )
    (net (code "104") (name "unconnected-(J1-Pad79)") (class "Default")
      (node (ref "J1") (pin "79") (pinfunction "79_79") (pintype "passive"))
    )
    (net (code "105") (name "unconnected-(J1-Pad81)") (class "Default")
      (node (ref "J1") (pin "81") (pinfunction "81_81") (pintype "passive"))
    )
    (net (code "106") (name "unconnected-(J1-Pad85)") (class "Default")
      (node (ref "J1") (pin "85") (pinfunction "85_85") (pintype "passive"))
    )
    (net (code "107") (name "unconnected-(J1-Pad86)") (class "Default")
      (node (ref "J1") (pin "86") (pinfunction "86_86") (pintype "passive"))
    )
    (net (code "108") (name "unconnected-(J1-Pad87)") (class "Default")
      (node (ref "J1") (pin "87") (pinfunction "87_87") (pintype "passive"))
    )
    (net (code "109") (name "unconnected-(J1-Pad88)") (class "Default")
      (node (ref "J1") (pin "88") (pinfunction "88_88") (pintype "passive"))
    )
    (net (code "110") (name "unconnected-(J1-Pad89)") (class "Default")
      (node (ref "J1") (pin "89") (pinfunction "89_89") (pintype "passive"))
    )
    (net (code "111") (name "unconnected-(J1-Pad90)") (class "Default")
      (node (ref "J1") (pin "90") (pinfunction "90_90") (pintype "passive"))
    )
    (net (code "112") (name "unconnected-(J1-Pad91)") (class "Default")
      (node (ref "J1") (pin "91") (pinfunction "91_91") (pintype "passive"))
    )
    (net (code "113") (name "unconnected-(J1-Pad92)") (class "Default")
      (node (ref "J1") (pin "92") (pinfunction "92_92") (pintype "passive"))
    )
    (net (code "114") (name "unconnected-(J1-Pad95)") (class "Default")
      (node (ref "J1") (pin "95") (pinfunction "95_95") (pintype "passive"))
    )
    (net (code "115") (name "unconnected-(J1-Pad96)") (class "Default")
      (node (ref "J1") (pin "96") (pinfunction "96_96") (pintype "passive"))
    )
    (net (code "116") (name "unconnected-(J1-Pad97)") (class "Default")
      (node (ref "J1") (pin "97") (pinfunction "97_97") (pintype "passive"))
    )
    (net (code "117") (name "unconnected-(J1-Pad98)") (class "Default")
      (node (ref "J1") (pin "98") (pinfunction "98_98") (pintype "passive"))
    )
    (net (code "118") (name "unconnected-(J1-Pad99)") (class "Default")
      (node (ref "J1") (pin "99") (pinfunction "99_99") (pintype "passive"))
    )
    (net (code "119") (name "unconnected-(J1-Pad100)") (class "Default")
      (node (ref "J1") (pin "100") (pinfunction "100_100") (pintype "passive"))
    )
    (net (code "120") (name "unconnected-(J1-Pad101)") (class "Default")
      (node (ref "J1") (pin "101") (pinfunction "101_101") (pintype "passive"))
    )
    (net (code "121") (name "unconnected-(J1-Pad102)") (class "Default")
      (node (ref "J1") (pin "102") (pinfunction "102_102") (pintype "passive"))
    )
    (net (code "122") (name "unconnected-(P6-Pad1)") (class "Default")
      (node (ref "P6") (pin "1") (pinfunction "1_1") (pintype "passive"))
    )
    (net (code "123") (name "unconnected-(P6-Pad2)") (class "Default")
      (node (ref "P6") (pin "2") (pinfunction "2_2") (pintype "passive"))
    )
    (net (code "124") (name "unconnected-(P6-Pad3)") (class "Default")
      (node (ref "P6") (pin "3") (pinfunction "3_3") (pintype "passive"))
    )
    (net (code "125") (name "unconnected-(P6-Pad4)") (class "Default")
      (node (ref "P6") (pin "4") (pinfunction "4_4") (pintype "passive"))
    )
    (net (code "126") (name "unconnected-(P6-Pad5)") (class "Default")
      (node (ref "P6") (pin "5") (pinfunction "5_5") (pintype "passive"))
    )
    (net (code "127") (name "unconnected-(P6-Pad6)") (class "Default")
      (node (ref "P6") (pin "6") (pinfunction "6_6") (pintype "passive"))
    )
    (net (code "128") (name "unconnected-(P6-Pad7)") (class "Default")
      (node (ref "P6") (pin "7") (pinfunction "7_7") (pintype "passive"))
    )
    (net (code "129") (name "unconnected-(P6-Pad8)") (class "Default")
      (node (ref "P6") (pin "8") (pinfunction "8_8") (pintype "passive"))
    )
    (net (code "130") (name "unconnected-(P6-Pad9)") (class "Default")
      (node (ref "P6") (pin "9") (pinfunction "9_9") (pintype "passive"))
    )
    (net (code "131") (name "unconnected-(P6-Pad10)") (class "Default")
      (node (ref "P6") (pin "10") (pinfunction "10_10") (pintype "passive"))
    )
    (net (code "132") (name "unconnected-(P6-Pad11)") (class "Default")
      (node (ref "P6") (pin "11") (pinfunction "11_11") (pintype "passive"))
    )
    (net (code "133") (name "unconnected-(P6-Pad12)") (class "Default")
      (node (ref "P6") (pin "12") (pinfunction "12_12") (pintype "passive"))
    )
    (net (code "134") (name "unconnected-(RN5-1-Pad7)") (class "Default")
      (node (ref "RN5") (pin "7") (pinfunction "1_7") (pintype "passive"))
    )
    (net (code "135") (name "unconnected-(RN5-Pad1)") (class "Default")
      (node (ref "RN5") (pin "1") (pinfunction "1_1") (pintype "passive"))
    )
    (net (code "136") (name "unconnected-(RN5-Pad3)") (class "Default")
      (node (ref "RN5") (pin "3") (pinfunction "3_3") (pintype "passive"))
    )
    (net (code "137") (name "unconnected-(RN5-Pad5)") (class "Default")
      (node (ref "RN5") (pin "5") (pinfunction "5_5") (pintype "passive"))
    )
    (net (code "138") (name "unconnected-(RN6-1-Pad7)") (class "Default")
      (node (ref "RN6") (pin "7") (pinfunction "1_7") (pintype "passive"))
    )
    (net (code "139") (name "unconnected-(RN6-Pad1)") (class "Default")
      (node (ref "RN6") (pin "1") (pinfunction "1_1") (pintype "passive"))
    )
    (net (code "140") (name "unconnected-(RN6-Pad3)") (class "Default")
      (node (ref "RN6") (pin "3") (pinfunction "3_3") (pintype "passive"))
    )
    (net (code "141") (name "unconnected-(RN6-Pad5)") (class "Default")
      (node (ref "RN6") (pin "5") (pinfunction "5_5") (pintype "passive"))
    )
    (net (code "142") (name "unconnected-(RN7-1-Pad7)") (class "Default")
      (node (ref "RN7") (pin "7") (pinfunction "1_7") (pintype "passive"))
    )
    (net (code "143") (name "unconnected-(RN7-Pad1)") (class "Default")
      (node (ref "RN7") (pin "1") (pinfunction "1_1") (pintype "passive"))
    )
    (net (code "144") (name "unconnected-(RN7-Pad3)") (class "Default")
      (node (ref "RN7") (pin "3") (pinfunction "3_3") (pintype "passive"))
    )
    (net (code "145") (name "unconnected-(RN7-Pad5)") (class "Default")
      (node (ref "RN7") (pin "5") (pinfunction "5_5") (pintype "passive"))
    )
    (net (code "146") (name "unconnected-(U1-NC-Pad5)") (class "Default")
      (node (ref "U1") (pin "5") (pinfunction "NC_5") (pintype "passive"))
    )
    (net (code "147") (name "unconnected-(U1-VOSTRIM-Pad1)") (class "Default")
      (node (ref "U1") (pin "1") (pinfunction "VOSTRIM_1") (pintype "passive"))
    )
    (net (code "148") (name "unconnected-(U1-VOSTRIM-Pad8)") (class "Default")
      (node (ref "U1") (pin "8") (pinfunction "VOSTRIM_8") (pintype "passive"))
    )
    (net (code "149") (name "unconnected-(U4-B0-Pad3)") (class "Default")
      (node (ref "U4") (pin "3") (pinfunction "B0_3") (pintype "passive+no_connect"))
    )
  )
)
